# Target_Control_Remote.net
KiCad netlist of a schematic drawn in Altium Designer
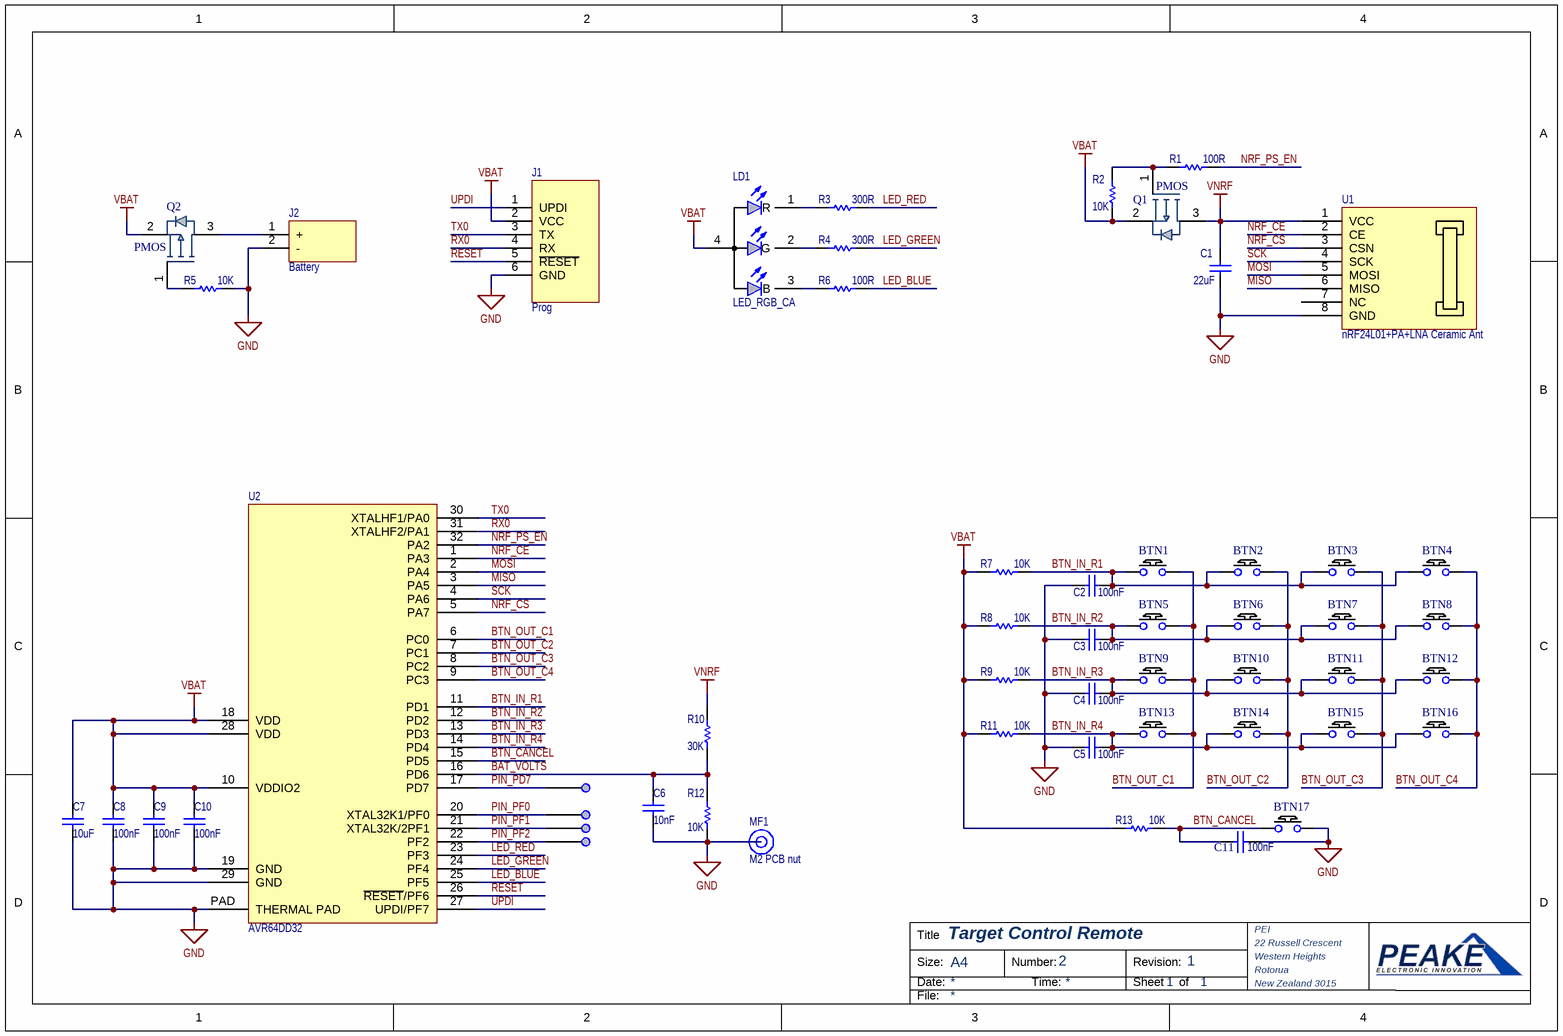
[diagram p0: Target Control Remote.SchDoc]

(export (version "E")
  (design (tool "Eeschema 10.0.6"))
  (components
    (comp (ref "BTN1")
      (value "Button")
      (footprint "PTS526 SK15 SMTR2 LFS SMD Tactile Push Button")
      (description "Momentary push button")
      (libsource (lib "Scion Research") (part "CMP-011-00013-6"))
    )
    (comp (ref "BTN2")
      (value "Button")
      (footprint "PTS526 SK15 SMTR2 LFS SMD Tactile Push Button")
      (description "Momentary push button")
      (libsource (lib "Scion Research") (part "CMP-011-00013-6"))
    )
    (comp (ref "BTN3")
      (value "Button")
      (footprint "PTS526 SK15 SMTR2 LFS SMD Tactile Push Button")
      (description "Momentary push button")
      (libsource (lib "Scion Research") (part "CMP-011-00013-6"))
    )
    (comp (ref "BTN4")
      (value "Button")
      (footprint "PTS526 SK15 SMTR2 LFS SMD Tactile Push Button")
      (description "Momentary push button")
      (libsource (lib "Scion Research") (part "CMP-011-00013-6"))
    )
    (comp (ref "BTN5")
      (value "Button")
      (footprint "PTS526 SK15 SMTR2 LFS SMD Tactile Push Button")
      (description "Momentary push button")
      (libsource (lib "Scion Research") (part "CMP-011-00013-6"))
    )
    (comp (ref "BTN6")
      (value "Button")
      (footprint "PTS526 SK15 SMTR2 LFS SMD Tactile Push Button")
      (description "Momentary push button")
      (libsource (lib "Scion Research") (part "CMP-011-00013-6"))
    )
    (comp (ref "BTN7")
      (value "Button")
      (footprint "PTS526 SK15 SMTR2 LFS SMD Tactile Push Button")
      (description "Momentary push button")
      (libsource (lib "Scion Research") (part "CMP-011-00013-6"))
    )
    (comp (ref "BTN8")
      (value "Button")
      (footprint "PTS526 SK15 SMTR2 LFS SMD Tactile Push Button")
      (description "Momentary push button")
      (libsource (lib "Scion Research") (part "CMP-011-00013-6"))
    )
    (comp (ref "BTN9")
      (value "Button")
      (footprint "PTS526 SK15 SMTR2 LFS SMD Tactile Push Button")
      (description "Momentary push button")
      (libsource (lib "Scion Research") (part "CMP-011-00013-6"))
    )
    (comp (ref "BTN10")
      (value "Button")
      (footprint "PTS526 SK15 SMTR2 LFS SMD Tactile Push Button")
      (description "Momentary push button")
      (libsource (lib "Scion Research") (part "CMP-011-00013-6"))
    )
    (comp (ref "BTN11")
      (value "Button")
      (footprint "PTS526 SK15 SMTR2 LFS SMD Tactile Push Button")
      (description "Momentary push button")
      (libsource (lib "Scion Research") (part "CMP-011-00013-6"))
    )
    (comp (ref "BTN12")
      (value "Button")
      (footprint "PTS526 SK15 SMTR2 LFS SMD Tactile Push Button")
      (description "Momentary push button")
      (libsource (lib "Scion Research") (part "CMP-011-00013-6"))
    )
    (comp (ref "BTN13")
      (value "Button")
      (footprint "PTS526 SK15 SMTR2 LFS SMD Tactile Push Button")
      (description "Momentary push button")
      (libsource (lib "Scion Research") (part "CMP-011-00013-6"))
    )
    (comp (ref "BTN14")
      (value "Button")
      (footprint "PTS526 SK15 SMTR2 LFS SMD Tactile Push Button")
      (description "Momentary push button")
      (libsource (lib "Scion Research") (part "CMP-011-00013-6"))
    )
    (comp (ref "BTN15")
      (value "Button")
      (footprint "PTS526 SK15 SMTR2 LFS SMD Tactile Push Button")
      (description "Momentary push button")
      (libsource (lib "Scion Research") (part "CMP-011-00013-6"))
    )
    (comp (ref "BTN16")
      (value "Button")
      (footprint "PTS526 SK15 SMTR2 LFS SMD Tactile Push Button")
      (description "Momentary push button")
      (libsource (lib "Scion Research") (part "CMP-011-00013-6"))
    )
    (comp (ref "BTN17")
      (value "Button")
      (footprint "PTS526 SK15 SMTR2 LFS SMD Tactile Push Button")
      (description "Momentary push button")
      (libsource (lib "Scion Research") (part "CMP-011-00013-6"))
    )
    (comp (ref "C1")
      (value "22uF")
      (footprint "0805_CAP")
      (description "SMD Capacitor")
      (fields (field (name "Comment") "Capacitor"))
      (libsource (lib "Scion Research") (part "CMP-019-00005-2"))
    )
    (comp (ref "C2")
      (value "100nF")
      (footprint "0603_CAP")
      (description "SMD Capacitor")
      (fields (field (name "Comment") "CMP-001-00172-1"))
      (libsource (lib "Scion Research") (part "CMP-019-00005-2"))
    )
    (comp (ref "C3")
      (value "100nF")
      (footprint "0603_CAP")
      (description "SMD Capacitor")
      (fields (field (name "Comment") "Capacitor"))
      (libsource (lib "Scion Research") (part "CMP-019-00005-2"))
    )
    (comp (ref "C4")
      (value "100nF")
      (footprint "0603_CAP")
      (description "SMD Capacitor")
      (fields (field (name "Comment") "Capacitor"))
      (libsource (lib "Scion Research") (part "CMP-019-00005-2"))
    )
    (comp (ref "C5")
      (value "100nF")
      (footprint "0603_CAP")
      (description "SMD Capacitor")
      (fields (field (name "Comment") "Capacitor"))
      (libsource (lib "Scion Research") (part "CMP-019-00005-2"))
    )
    (comp (ref "C6")
      (value "10nF")
      (footprint "0603_CAP")
      (description "SMD Capacitor")
      (fields (field (name "Comment") "Capacitor"))
      (libsource (lib "Scion Research") (part "CMP-019-00005-2"))
    )
    (comp (ref "C7")
      (value "10uF")
      (footprint "0603_CAP")
      (description "SMD Capacitor")
      (fields (field (name "Comment") "Capacitor"))
      (libsource (lib "Scion Research") (part "CMP-019-00005-2"))
    )
    (comp (ref "C8")
      (value "100nF")
      (footprint "0603_CAP")
      (description "SMD Capacitor")
      (fields (field (name "Comment") "Capacitor"))
      (libsource (lib "Scion Research") (part "CMP-019-00005-2"))
    )
    (comp (ref "C9")
      (value "100nF")
      (footprint "0603_CAP")
      (description "SMD Capacitor")
      (fields (field (name "Comment") "Capacitor"))
      (libsource (lib "Scion Research") (part "CMP-019-00005-2"))
    )
    (comp (ref "C10")
      (value "100nF")
      (footprint "0603_CAP")
      (description "SMD Capacitor")
      (fields (field (name "Comment") "Capacitor"))
      (libsource (lib "Scion Research") (part "CMP-019-00005-2"))
    )
    (comp (ref "C11")
      (value "100nF")
      (footprint "0603_CAP")
      (description "SMD Capacitor")
      (fields (field (name "Comment") "Capacitor"))
      (libsource (lib "Scion Research") (part "CMP-019-00005-2"))
    )
    (comp (ref "J1")
      (value "Prog")
      (footprint "DIP6")
      (description "6 Pin Connector")
      (libsource (lib "Scion Research") (part "CMP-002-00081-5"))
    )
    (comp (ref "J2")
      (value "Battery")
      (footprint "2mm RA S2B-PH-K-S")
      (description "2 Pin Connector")
      (libsource (lib "Scion Research") (part "CMP-002-00074-8"))
    )
    (comp (ref "J3")
      (value "CMP-00044-2")
      (footprint "Prog Pad 1.5 x 2.5mm")
      (description "Programmer pogo-pin interface pad (or test pad)")
      (libsource (lib "Scion Research") (part "CMP-00044-2"))
    )
    (comp (ref "J4")
      (value "CMP-00044-2")
      (footprint "Prog Pad 1.5 x 2.5mm")
      (description "Programmer pogo-pin interface pad (or test pad)")
      (libsource (lib "Scion Research") (part "CMP-00044-2"))
    )
    (comp (ref "J5")
      (value "CMP-00044-2")
      (footprint "Prog Pad 1.5 x 2.5mm")
      (description "Programmer pogo-pin interface pad (or test pad)")
      (libsource (lib "Scion Research") (part "CMP-00044-2"))
    )
    (comp (ref "J6")
      (value "CMP-00044-2")
      (footprint "Prog Pad 1.5 x 2.5mm")
      (description "Programmer pogo-pin interface pad (or test pad)")
      (libsource (lib "Scion Research") (part "CMP-00044-2"))
    )
    (comp (ref "LD1")
      (value "LED_RGB_CA")
      (footprint "LED_RGB_CA")
      (description "Common Annode SMD RGB LED")
      (libsource (lib "Scion Research") (part "CMP-007-00037-1"))
    )
    (comp (ref "MF1")
      (value "M2 PCB nut")
      (footprint "PCB Nut M2-TH")
      (description "SMD or through hole soldered PCB nut")
      (libsource (lib "Scion Research") (part "CMP-00059-2"))
    )
    (comp (ref "Q1")
      (value "PMOS")
      (footprint "SOT-23-PMOS")
      (description "P Channel MOSFET")
      (libsource (lib "Scion Research") (part "CMP-004-0033-1"))
    )
    (comp (ref "Q2")
      (value "PMOS")
      (footprint "SOT-23-PMOS")
      (description "P Channel MOSFET")
      (libsource (lib "Scion Research") (part "CMP-004-0033-1"))
    )
    (comp (ref "R1")
      (value "100R")
      (footprint "0603_RES")
      (description "SMD Resistor")
      (fields (field (name "Comment") "Resistor"))
      (libsource (lib "Scion Research") (part "CMP-009-00177-2"))
    )
    (comp (ref "R2")
      (value "10K")
      (footprint "0603_RES")
      (description "SMD Resistor")
      (fields (field (name "Comment") "Resistor"))
      (libsource (lib "Scion Research") (part "CMP-009-00177-2"))
    )
    (comp (ref "R3")
      (value "300R")
      (footprint "0603_RES")
      (description "SMD Resistor")
      (fields (field (name "Comment") "Resistor"))
      (libsource (lib "Scion Research") (part "CMP-009-00177-2"))
    )
    (comp (ref "R4")
      (value "300R")
      (footprint "0603_RES")
      (description "SMD Resistor")
      (fields (field (name "Comment") "Resistor"))
      (libsource (lib "Scion Research") (part "CMP-009-00177-2"))
    )
    (comp (ref "R5")
      (value "10K")
      (footprint "0603_RES")
      (description "SMD Resistor")
      (fields (field (name "Comment") "Resistor"))
      (libsource (lib "Scion Research") (part "CMP-009-00177-2"))
    )
    (comp (ref "R6")
      (value "100R")
      (footprint "0603_RES")
      (description "SMD Resistor")
      (fields (field (name "Comment") "Resistor"))
      (libsource (lib "Scion Research") (part "CMP-009-00177-2"))
    )
    (comp (ref "R7")
      (value "10K")
      (footprint "0603_RES")
      (description "SMD Resistor")
      (fields (field (name "Comment") "Resistor"))
      (libsource (lib "Scion Research") (part "CMP-009-00177-2"))
    )
    (comp (ref "R8")
      (value "10K")
      (footprint "0603_RES")
      (description "SMD Resistor")
      (fields (field (name "Comment") "Resistor"))
      (libsource (lib "Scion Research") (part "CMP-009-00177-2"))
    )
    (comp (ref "R9")
      (value "10K")
      (footprint "0603_RES")
      (description "SMD Resistor")
      (fields (field (name "Comment") "Resistor"))
      (libsource (lib "Scion Research") (part "CMP-009-00177-2"))
    )
    (comp (ref "R10")
      (value "30K")
      (footprint "0603_RES")
      (description "SMD Resistor")
      (fields (field (name "Comment") "Resistor"))
      (libsource (lib "Scion Research") (part "CMP-009-00177-2"))
    )
    (comp (ref "R11")
      (value "10K")
      (footprint "0603_RES")
      (description "SMD Resistor")
      (fields (field (name "Comment") "Resistor"))
      (libsource (lib "Scion Research") (part "CMP-009-00177-2"))
    )
    (comp (ref "R12")
      (value "10K")
      (footprint "0603_RES")
      (description "SMD Resistor")
      (fields (field (name "Comment") "Resistor"))
      (libsource (lib "Scion Research") (part "CMP-009-00177-2"))
    )
    (comp (ref "R13")
      (value "10K")
      (footprint "0603_RES")
      (description "SMD Resistor")
      (fields (field (name "Comment") "Resistor"))
      (libsource (lib "Scion Research") (part "CMP-009-00177-2"))
    )
    (comp (ref "U1")
      (value "nRF24L01+PA+LNA Ceramic Ant")
      (footprint "nRF24L01+PA+LNA Ceramic Antenna-Footprint-1")
      (description "nRF24L01+PA+LNA Ceramic Antenna SMD module YJ-13039")
      (libsource (lib "Scion Research") (part "CMP-00025-00003-2"))
    )
    (comp (ref "U2")
      (value "AVR64DD32")
      (footprint "32P VQFN")
      (libsource (lib "Scion Research") (part "CMP-00041-1"))
    )
  )
  (nets
    (net (code "1") (name "/BAT_VOLTS") (class "Default")
      (node (ref "C6") (pin "2") (pinfunction "2_2") (pintype "passive"))
      (node (ref "R10") (pin "1") (pinfunction "1_1") (pintype "passive"))
      (node (ref "R12") (pin "2") (pinfunction "2_2") (pintype "passive"))
      (node (ref "U2") (pin "16") (pinfunction "PD6_16") (pintype "passive"))
    )
    (net (code "2") (name "/BTN_CANCEL") (class "Default")
      (node (ref "BTN17") (pin "1") (pinfunction "*_1") (pintype "passive"))
      (node (ref "C11") (pin "2") (pinfunction "2_2") (pintype "passive"))
      (node (ref "R13") (pin "2") (pinfunction "2_2") (pintype "passive"))
      (node (ref "U2") (pin "15") (pinfunction "PD5_15") (pintype "passive"))
    )
    (net (code "3") (name "/BTN_IN_R1") (class "Default")
      (node (ref "BTN1") (pin "1") (pinfunction "*_1") (pintype "passive"))
      (node (ref "BTN2") (pin "1") (pinfunction "*_1") (pintype "passive"))
      (node (ref "BTN3") (pin "1") (pinfunction "*_1") (pintype "passive"))
      (node (ref "BTN4") (pin "1") (pinfunction "*_1") (pintype "passive"))
      (node (ref "C2") (pin "1") (pinfunction "1_1") (pintype "passive"))
      (node (ref "R7") (pin "2") (pinfunction "2_2") (pintype "passive"))
      (node (ref "U2") (pin "11") (pinfunction "PD1_11") (pintype "passive"))
    )
    (net (code "4") (name "/BTN_IN_R2") (class "Default")
      (node (ref "BTN5") (pin "1") (pinfunction "*_1") (pintype "passive"))
      (node (ref "BTN6") (pin "1") (pinfunction "*_1") (pintype "passive"))
      (node (ref "BTN7") (pin "1") (pinfunction "*_1") (pintype "passive"))
      (node (ref "BTN8") (pin "1") (pinfunction "*_1") (pintype "passive"))
      (node (ref "C3") (pin "1") (pinfunction "1_1") (pintype "passive"))
      (node (ref "R8") (pin "2") (pinfunction "2_2") (pintype "passive"))
      (node (ref "U2") (pin "12") (pinfunction "PD2_12") (pintype "passive"))
    )
    (net (code "5") (name "/BTN_IN_R3") (class "Default")
      (node (ref "BTN10") (pin "1") (pinfunction "*_1") (pintype "passive"))
      (node (ref "BTN11") (pin "1") (pinfunction "*_1") (pintype "passive"))
      (node (ref "BTN12") (pin "1") (pinfunction "*_1") (pintype "passive"))
      (node (ref "BTN9") (pin "1") (pinfunction "*_1") (pintype "passive"))
      (node (ref "C4") (pin "1") (pinfunction "1_1") (pintype "passive"))
      (node (ref "R9") (pin "2") (pinfunction "2_2") (pintype "passive"))
      (node (ref "U2") (pin "13") (pinfunction "PD3_13") (pintype "passive"))
    )
    (net (code "6") (name "/BTN_IN_R4") (class "Default")
      (node (ref "BTN13") (pin "1") (pinfunction "*_1") (pintype "passive"))
      (node (ref "BTN14") (pin "1") (pinfunction "*_1") (pintype "passive"))
      (node (ref "BTN15") (pin "1") (pinfunction "*_1") (pintype "passive"))
      (node (ref "BTN16") (pin "1") (pinfunction "*_1") (pintype "passive"))
      (node (ref "C5") (pin "1") (pinfunction "1_1") (pintype "passive"))
      (node (ref "R11") (pin "2") (pinfunction "2_2") (pintype "passive"))
      (node (ref "U2") (pin "14") (pinfunction "PD4_14") (pintype "passive"))
    )
    (net (code "7") (name "/BTN_OUT_C1") (class "Default")
      (node (ref "BTN1") (pin "2") (pinfunction "*_2") (pintype "passive"))
      (node (ref "BTN13") (pin "2") (pinfunction "*_2") (pintype "passive"))
      (node (ref "BTN5") (pin "2") (pinfunction "*_2") (pintype "passive"))
      (node (ref "BTN9") (pin "2") (pinfunction "*_2") (pintype "passive"))
      (node (ref "U2") (pin "6") (pinfunction "PC0_6") (pintype "passive"))
    )
    (net (code "8") (name "/BTN_OUT_C2") (class "Default")
      (node (ref "BTN10") (pin "2") (pinfunction "*_2") (pintype "passive"))
      (node (ref "BTN14") (pin "2") (pinfunction "*_2") (pintype "passive"))
      (node (ref "BTN2") (pin "2") (pinfunction "*_2") (pintype "passive"))
      (node (ref "BTN6") (pin "2") (pinfunction "*_2") (pintype "passive"))
      (node (ref "U2") (pin "7") (pinfunction "PC1_7") (pintype "passive"))
    )
    (net (code "9") (name "/BTN_OUT_C3") (class "Default")
      (node (ref "BTN11") (pin "2") (pinfunction "*_2") (pintype "passive"))
      (node (ref "BTN15") (pin "2") (pinfunction "*_2") (pintype "passive"))
      (node (ref "BTN3") (pin "2") (pinfunction "*_2") (pintype "passive"))
      (node (ref "BTN7") (pin "2") (pinfunction "*_2") (pintype "passive"))
      (node (ref "U2") (pin "8") (pinfunction "PC2_8") (pintype "passive"))
    )
    (net (code "10") (name "/BTN_OUT_C4") (class "Default")
      (node (ref "BTN12") (pin "2") (pinfunction "*_2") (pintype "passive"))
      (node (ref "BTN16") (pin "2") (pinfunction "*_2") (pintype "passive"))
      (node (ref "BTN4") (pin "2") (pinfunction "*_2") (pintype "passive"))
      (node (ref "BTN8") (pin "2") (pinfunction "*_2") (pintype "passive"))
      (node (ref "U2") (pin "9") (pinfunction "PC3_9") (pintype "passive"))
    )
    (net (code "11") (name "/LED_BLUE") (class "Default")
      (node (ref "R6") (pin "2") (pinfunction "2_2") (pintype "passive"))
      (node (ref "U2") (pin "25") (pinfunction "PF5_25") (pintype "passive"))
    )
    (net (code "12") (name "/LED_GREEN") (class "Default")
      (node (ref "R4") (pin "2") (pinfunction "2_2") (pintype "passive"))
      (node (ref "U2") (pin "24") (pinfunction "PF4_24") (pintype "passive"))
    )
    (net (code "13") (name "/LED_RED") (class "Default")
      (node (ref "R3") (pin "2") (pinfunction "2_2") (pintype "passive"))
      (node (ref "U2") (pin "23") (pinfunction "PF3_23") (pintype "passive"))
    )
    (net (code "14") (name "/MISO") (class "Default")
      (node (ref "U1") (pin "6") (pinfunction "MISO_6") (pintype "passive"))
      (node (ref "U2") (pin "3") (pinfunction "PA5_3") (pintype "passive"))
    )
    (net (code "15") (name "/MOSI") (class "Default")
      (node (ref "U1") (pin "5") (pinfunction "MOSI_5") (pintype "passive"))
      (node (ref "U2") (pin "2") (pinfunction "PA4_2") (pintype "passive"))
    )
    (net (code "16") (name "/NRF_CE") (class "Default")
      (node (ref "U1") (pin "2") (pinfunction "CE_2") (pintype "passive"))
      (node (ref "U2") (pin "1") (pinfunction "PA3_1") (pintype "passive"))
    )
    (net (code "17") (name "/NRF_CS") (class "Default")
      (node (ref "U1") (pin "3") (pinfunction "CSN_3") (pintype "passive"))
      (node (ref "U2") (pin "5") (pinfunction "PA7_5") (pintype "passive"))
    )
    (net (code "18") (name "/NRF_PS_EN") (class "Default")
      (node (ref "R1") (pin "2") (pinfunction "2_2") (pintype "passive"))
      (node (ref "U2") (pin "32") (pinfunction "PA2_32") (pintype "passive"))
    )
    (net (code "19") (name "/PIN_PD7") (class "Default")
      (node (ref "J3") (pin "1") (pinfunction "1_1") (pintype "passive"))
      (node (ref "U2") (pin "17") (pinfunction "PD7_17") (pintype "passive"))
    )
    (net (code "20") (name "/PIN_PF0") (class "Default")
      (node (ref "J4") (pin "1") (pinfunction "1_1") (pintype "passive"))
      (node (ref "U2") (pin "20") (pinfunction "XTAL32K1/PF0_20") (pintype "passive"))
    )
    (net (code "21") (name "/PIN_PF1") (class "Default")
      (node (ref "J5") (pin "1") (pinfunction "1_1") (pintype "passive"))
      (node (ref "U2") (pin "21") (pinfunction "XTAL32K/2PF1_21") (pintype "passive"))
    )
    (net (code "22") (name "/PIN_PF2") (class "Default")
      (node (ref "J6") (pin "1") (pinfunction "1_1") (pintype "passive"))
      (node (ref "U2") (pin "22") (pinfunction "PF2_22") (pintype "passive"))
    )
    (net (code "23") (name "/RX0") (class "Default")
      (node (ref "J1") (pin "4") (pinfunction "RX_4") (pintype "passive"))
      (node (ref "U2") (pin "31") (pinfunction "XTALHF2/PA1_31") (pintype "passive"))
    )
    (net (code "24") (name "/SCK") (class "Default")
      (node (ref "U1") (pin "4") (pinfunction "SCK_4") (pintype "passive"))
      (node (ref "U2") (pin "4") (pinfunction "PA6_4") (pintype "passive"))
    )
    (net (code "25") (name "/TX0") (class "Default")
      (node (ref "J1") (pin "3") (pinfunction "TX_3") (pintype "passive"))
      (node (ref "U2") (pin "30") (pinfunction "XTALHF1/PA0_30") (pintype "passive"))
    )
    (net (code "26") (name "/UPDI") (class "Default")
      (node (ref "J1") (pin "1") (pinfunction "UPDI_1") (pintype "passive"))
      (node (ref "U2") (pin "27") (pinfunction "UPDI/PF7_27") (pintype "passive"))
    )
    (net (code "27") (name "/~{RESET}") (class "Default")
      (node (ref "J1") (pin "5") (pinfunction "~{RESET}_5") (pintype "passive"))
      (node (ref "U2") (pin "26") (pinfunction "~{RESET}/PF6_26") (pintype "passive"))
    )
    (net (code "28") (name "GND") (class "Default")
      (node (ref "BTN17") (pin "2") (pinfunction "*_2") (pintype "passive"))
      (node (ref "C1") (pin "1") (pinfunction "1_1") (pintype "passive"))
      (node (ref "C10") (pin "1") (pinfunction "1_1") (pintype "passive"))
      (node (ref "C11") (pin "1") (pinfunction "1_1") (pintype "passive"))
      (node (ref "C2") (pin "2") (pinfunction "2_2") (pintype "passive"))
      (node (ref "C3") (pin "2") (pinfunction "2_2") (pintype "passive"))
      (node (ref "C4") (pin "2") (pinfunction "2_2") (pintype "passive"))
      (node (ref "C5") (pin "2") (pinfunction "2_2") (pintype "passive"))
      (node (ref "C6") (pin "1") (pinfunction "1_1") (pintype "passive"))
      (node (ref "C7") (pin "1") (pinfunction "1_1") (pintype "passive"))
      (node (ref "C8") (pin "1") (pinfunction "1_1") (pintype "passive"))
      (node (ref "C9") (pin "1") (pinfunction "1_1") (pintype "passive"))
      (node (ref "J1") (pin "6") (pinfunction "GND_6") (pintype "passive"))
      (node (ref "J2") (pin "2") (pinfunction "-_2") (pintype "passive"))
      (node (ref "MF1") (pin "1") (pintype "passive"))
      (node (ref "R12") (pin "1") (pinfunction "1_1") (pintype "passive"))
      (node (ref "R5") (pin "2") (pinfunction "2_2") (pintype "passive"))
      (node (ref "U1") (pin "8") (pinfunction "GND_8") (pintype "passive"))
      (node (ref "U2") (pin "19") (pinfunction "GND_19") (pintype "passive"))
      (node (ref "U2") (pin "29") (pinfunction "GND_29") (pintype "passive"))
      (node (ref "U2") (pin "PAD") (pinfunction "THERMAL_PAD_PAD") (pintype "passive"))
    )
    (net (code "29") (name "Net-(J2-+)") (class "Default")
      (node (ref "J2") (pin "1") (pinfunction "+_1") (pintype "passive"))
      (node (ref "Q2") (pin "3") (pinfunction "D_3") (pintype "passive"))
    )
    (net (code "30") (name "Net-(LD1-B)") (class "Default")
      (node (ref "LD1") (pin "3") (pinfunction "B_3") (pintype "passive"))
      (node (ref "R6") (pin "1") (pinfunction "1_1") (pintype "passive"))
    )
    (net (code "31") (name "Net-(LD1-G)") (class "Default")
      (node (ref "LD1") (pin "2") (pinfunction "G_2") (pintype "passive"))
      (node (ref "R4") (pin "1") (pinfunction "1_1") (pintype "passive"))
    )
    (net (code "32") (name "Net-(LD1-R)") (class "Default")
      (node (ref "LD1") (pin "1") (pinfunction "R_1") (pintype "passive"))
      (node (ref "R3") (pin "1") (pinfunction "1_1") (pintype "passive"))
    )
    (net (code "33") (name "Net-(Q1-G)") (class "Default")
      (node (ref "Q1") (pin "1") (pinfunction "G_1") (pintype "passive"))
      (node (ref "R1") (pin "1") (pinfunction "1_1") (pintype "passive"))
      (node (ref "R2") (pin "2") (pinfunction "2_2") (pintype "passive"))
    )
    (net (code "34") (name "Net-(Q2-G)") (class "Default")
      (node (ref "Q2") (pin "1") (pinfunction "G_1") (pintype "passive"))
      (node (ref "R5") (pin "1") (pinfunction "1_1") (pintype "passive"))
    )
    (net (code "35") (name "VBAT") (class "Default")
      (node (ref "C10") (pin "2") (pinfunction "2_2") (pintype "passive"))
      (node (ref "C7") (pin "2") (pinfunction "2_2") (pintype "passive"))
      (node (ref "C8") (pin "2") (pinfunction "2_2") (pintype "passive"))
      (node (ref "C9") (pin "2") (pinfunction "2_2") (pintype "passive"))
      (node (ref "J1") (pin "2") (pinfunction "VCC_2") (pintype "passive"))
      (node (ref "LD1") (pin "4") (pinfunction "A_4") (pintype "power_in"))
      (node (ref "Q1") (pin "2") (pinfunction "S_2") (pintype "passive"))
      (node (ref "Q2") (pin "2") (pinfunction "S_2") (pintype "passive"))
      (node (ref "R11") (pin "1") (pinfunction "1_1") (pintype "passive"))
      (node (ref "R13") (pin "1") (pinfunction "1_1") (pintype "passive"))
      (node (ref "R2") (pin "1") (pinfunction "1_1") (pintype "passive"))
      (node (ref "R7") (pin "1") (pinfunction "1_1") (pintype "passive"))
      (node (ref "R8") (pin "1") (pinfunction "1_1") (pintype "passive"))
      (node (ref "R9") (pin "1") (pinfunction "1_1") (pintype "passive"))
      (node (ref "U2") (pin "10") (pinfunction "VDDIO2_10") (pintype "passive"))
      (node (ref "U2") (pin "18") (pinfunction "VDD_18") (pintype "passive"))
      (node (ref "U2") (pin "28") (pinfunction "VDD_28") (pintype "passive"))
    )
    (net (code "36") (name "VNRF") (class "Default")
      (node (ref "C1") (pin "2") (pinfunction "2_2") (pintype "passive"))
      (node (ref "Q1") (pin "3") (pinfunction "D_3") (pintype "passive"))
      (node (ref "R10") (pin "2") (pinfunction "2_2") (pintype "passive"))
      (node (ref "U1") (pin "1") (pinfunction "VCC_1") (pintype "passive"))
    )
    (net (code "37") (name "unconnected-(U1-NC-Pad7)") (class "Default")
      (node (ref "U1") (pin "7") (pinfunction "NC_7") (pintype "passive"))
    )
  )
)
